# peripherals.net
KiCad netlist of a schematic drawn in Altium Designer
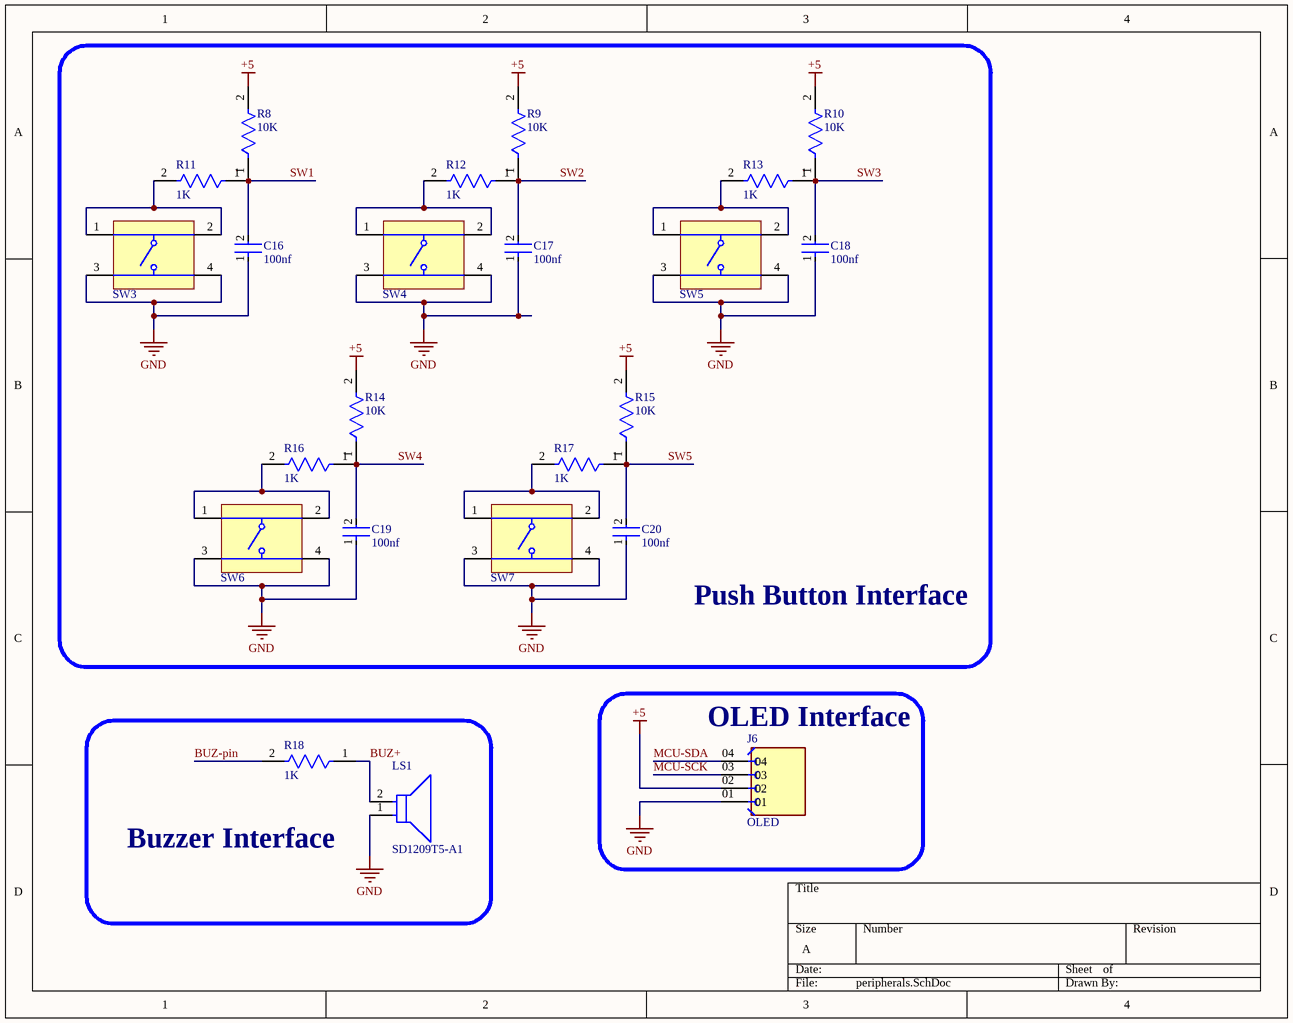
[diagram p0: peripherals.SchDoc]

(export (version "E")
  (design (tool "Eeschema 10.0.6"))
  (components
    (comp (ref "C16")
      (value "100nf")
      (footprint "FP-CC0805-0_85-MFG")
      (description "CAP CER 0.1UF 50V X7R 0805")
      (fields (field (name "TOLERANCE") "0.1") (field (name "MANUFACTURER PART NUMBER") "CC0805KRX7R9BB104"))
      (libsource (lib "Altium Content Vault") (part "11868f565c42a9108669ba33697ecf6"))
    )
    (comp (ref "C17")
      (value "100nf")
      (footprint "FP-CC0805-0_85-MFG")
      (description "CAP CER 0.1UF 50V X7R 0805")
      (fields (field (name "TOLERANCE") "0.1") (field (name "MANUFACTURER PART NUMBER") "CC0805KRX7R9BB104"))
      (libsource (lib "Altium Content Vault") (part "11868f565c42a9108669ba33697ecf6"))
    )
    (comp (ref "C18")
      (value "100nf")
      (footprint "FP-CC0805-0_85-MFG")
      (description "CAP CER 0.1UF 50V X7R 0805")
      (fields (field (name "TOLERANCE") "0.1") (field (name "MANUFACTURER PART NUMBER") "CC0805KRX7R9BB104"))
      (libsource (lib "Altium Content Vault") (part "11868f565c42a9108669ba33697ecf6"))
    )
    (comp (ref "C19")
      (value "100nf")
      (footprint "FP-CC0805-0_85-MFG")
      (description "CAP CER 0.1UF 50V X7R 0805")
      (fields (field (name "TOLERANCE") "0.1") (field (name "MANUFACTURER PART NUMBER") "CC0805KRX7R9BB104"))
      (libsource (lib "Altium Content Vault") (part "11868f565c42a9108669ba33697ecf6"))
    )
    (comp (ref "C20")
      (value "100nf")
      (footprint "FP-CC0805-0_85-MFG")
      (description "CAP CER 0.1UF 50V X7R 0805")
      (fields (field (name "TOLERANCE") "0.1") (field (name "MANUFACTURER PART NUMBER") "CC0805KRX7R9BB104"))
      (libsource (lib "Altium Content Vault") (part "11868f565c42a9108669ba33697ecf6"))
    )
    (comp (ref "J6")
      (value "OLED")
      (footprint "AMPHENOL_75915-804")
      (fields (field (name "MF") "Amphenol") (field (name "MP") "75915-804"))
      (libsource (lib "1x4 female pin header") (part "75915-804"))
    )
    (comp (ref "LS1")
      (value "SD1209T5-A1")
      (footprint "FP-SD1209-MFG")
      (description "AUDIO MAGNETIC XDCR 3-6V TH")
      (libsource (lib "Altium Content Vault") (part "1973c4b650225fd2ddacaff6b763965"))
    )
    (comp (ref "R8")
      (value "10K")
      (footprint "FP-CRCW0805-e3-MFG")
      (description "RES Thick Film, 100kΩ, 1%, 0.125W, 100ppm/°C, 0805")
      (fields (field (name "TOLERANCE") "1%"))
      (libsource (lib "Altium Content Vault") (part "1029c3af85768c4190bb7ad29bc67b5"))
    )
    (comp (ref "R9")
      (value "10K")
      (footprint "FP-CRCW0805-e3-MFG")
      (description "RES Thick Film, 100kΩ, 1%, 0.125W, 100ppm/°C, 0805")
      (fields (field (name "TOLERANCE") "1%"))
      (libsource (lib "Altium Content Vault") (part "1029c3af85768c4190bb7ad29bc67b5"))
    )
    (comp (ref "R10")
      (value "10K")
      (footprint "FP-CRCW0805-e3-MFG")
      (description "RES Thick Film, 100kΩ, 1%, 0.125W, 100ppm/°C, 0805")
      (fields (field (name "TOLERANCE") "1%"))
      (libsource (lib "Altium Content Vault") (part "1029c3af85768c4190bb7ad29bc67b5"))
    )
    (comp (ref "R11")
      (value "1K")
      (footprint "FP-CRCW0805-e3-MFG")
      (description "RES Thick Film, 100kΩ, 1%, 0.125W, 100ppm/°C, 0805")
      (fields (field (name "TOLERANCE") "1%"))
      (libsource (lib "Altium Content Vault") (part "1029c3af85768c4190bb7ad29bc67b5"))
    )
    (comp (ref "R12")
      (value "1K")
      (footprint "FP-CRCW0805-e3-MFG")
      (description "RES Thick Film, 100kΩ, 1%, 0.125W, 100ppm/°C, 0805")
      (fields (field (name "TOLERANCE") "1%"))
      (libsource (lib "Altium Content Vault") (part "1029c3af85768c4190bb7ad29bc67b5"))
    )
    (comp (ref "R13")
      (value "1K")
      (footprint "FP-CRCW0805-e3-MFG")
      (description "RES Thick Film, 100kΩ, 1%, 0.125W, 100ppm/°C, 0805")
      (fields (field (name "TOLERANCE") "1%"))
      (libsource (lib "Altium Content Vault") (part "1029c3af85768c4190bb7ad29bc67b5"))
    )
    (comp (ref "R14")
      (value "10K")
      (footprint "FP-CRCW0805-e3-MFG")
      (description "RES Thick Film, 100kΩ, 1%, 0.125W, 100ppm/°C, 0805")
      (fields (field (name "TOLERANCE") "1%"))
      (libsource (lib "Altium Content Vault") (part "1029c3af85768c4190bb7ad29bc67b5"))
    )
    (comp (ref "R15")
      (value "10K")
      (footprint "FP-CRCW0805-e3-MFG")
      (description "RES Thick Film, 100kΩ, 1%, 0.125W, 100ppm/°C, 0805")
      (fields (field (name "TOLERANCE") "1%"))
      (libsource (lib "Altium Content Vault") (part "1029c3af85768c4190bb7ad29bc67b5"))
    )
    (comp (ref "R16")
      (value "1K")
      (footprint "FP-CRCW0805-e3-MFG")
      (description "RES Thick Film, 100kΩ, 1%, 0.125W, 100ppm/°C, 0805")
      (fields (field (name "TOLERANCE") "1%"))
      (libsource (lib "Altium Content Vault") (part "1029c3af85768c4190bb7ad29bc67b5"))
    )
    (comp (ref "R17")
      (value "1K")
      (footprint "FP-CRCW0805-e3-MFG")
      (description "RES Thick Film, 100kΩ, 1%, 0.125W, 100ppm/°C, 0805")
      (fields (field (name "TOLERANCE") "1%"))
      (libsource (lib "Altium Content Vault") (part "1029c3af85768c4190bb7ad29bc67b5"))
    )
    (comp (ref "R18")
      (value "1K")
      (footprint "FP-CRCW0805-e3-MFG")
      (description "RES Thick Film, 100kΩ, 1%, 0.125W, 100ppm/°C, 0805")
      (fields (field (name "TOLERANCE") "1%"))
      (libsource (lib "Altium Content Vault") (part "1029c3af85768c4190bb7ad29bc67b5"))
    )
    (comp (ref "SW3")
      (value "FSM4JSMATR")
      (footprint "TECO-FSM4JSMATR_V")
      (description "Micro Miniature Push Button Switch FSM JSM, 50 mA, -35 to 85 degC, 4-Pin SMD, RoHS, Tape and Reel")
      (fields (field (name "MANUFACTURER") "TE Connectivity"))
      (libsource (lib "Altium Content Vault") (part "SW-SPST-4_A"))
    )
    (comp (ref "SW4")
      (value "FSM4JSMATR")
      (footprint "TECO-FSM4JSMATR_V")
      (description "Micro Miniature Push Button Switch FSM JSM, 50 mA, -35 to 85 degC, 4-Pin SMD, RoHS, Tape and Reel")
      (fields (field (name "MANUFACTURER") "TE Connectivity"))
      (libsource (lib "Altium Content Vault") (part "SW-SPST-4_A"))
    )
    (comp (ref "SW5")
      (value "FSM4JSMATR")
      (footprint "TECO-FSM4JSMATR_V")
      (description "Micro Miniature Push Button Switch FSM JSM, 50 mA, -35 to 85 degC, 4-Pin SMD, RoHS, Tape and Reel")
      (fields (field (name "MANUFACTURER") "TE Connectivity"))
      (libsource (lib "Altium Content Vault") (part "SW-SPST-4_A"))
    )
    (comp (ref "SW6")
      (value "FSM4JSMATR")
      (footprint "TECO-FSM4JSMATR_V")
      (description "Micro Miniature Push Button Switch FSM JSM, 50 mA, -35 to 85 degC, 4-Pin SMD, RoHS, Tape and Reel")
      (fields (field (name "MANUFACTURER") "TE Connectivity"))
      (libsource (lib "Altium Content Vault") (part "SW-SPST-4_A"))
    )
    (comp (ref "SW7")
      (value "FSM4JSMATR")
      (footprint "TECO-FSM4JSMATR_V")
      (description "Micro Miniature Push Button Switch FSM JSM, 50 mA, -35 to 85 degC, 4-Pin SMD, RoHS, Tape and Reel")
      (fields (field (name "MANUFACTURER") "TE Connectivity"))
      (libsource (lib "Altium Content Vault") (part "SW-SPST-4_A"))
    )
  )
  (nets
    (net (code "1") (name "+5") (class "Default")
      (node (ref "J6") (pin "02") (pinfunction "02_02") (pintype "passive"))
      (node (ref "R10") (pin "2") (pinfunction "2_2") (pintype "passive"))
      (node (ref "R14") (pin "2") (pinfunction "2_2") (pintype "passive"))
      (node (ref "R15") (pin "2") (pinfunction "2_2") (pintype "passive"))
      (node (ref "R8") (pin "2") (pinfunction "2_2") (pintype "passive"))
      (node (ref "R9") (pin "2") (pinfunction "2_2") (pintype "passive"))
    )
    (net (code "2") (name "/BUZ+") (class "Default")
      (node (ref "LS1") (pin "2") (pinfunction "A_2") (pintype "passive"))
      (node (ref "R18") (pin "1") (pinfunction "1_1") (pintype "passive"))
    )
    (net (code "3") (name "/BUZ-pin") (class "Default")
      (node (ref "R18") (pin "2") (pinfunction "2_2") (pintype "passive"))
    )
    (net (code "4") (name "/MCU-SCK") (class "Default")
      (node (ref "J6") (pin "03") (pinfunction "03_03") (pintype "passive"))
    )
    (net (code "5") (name "/MCU-SDA") (class "Default")
      (node (ref "J6") (pin "04") (pinfunction "04_04") (pintype "passive"))
    )
    (net (code "6") (name "/SW1") (class "Default")
      (node (ref "C16") (pin "2") (pinfunction "2_2") (pintype "passive"))
      (node (ref "R11") (pin "1") (pinfunction "1_1") (pintype "passive"))
      (node (ref "R8") (pin "1") (pinfunction "1_1") (pintype "passive"))
    )
    (net (code "7") (name "/SW2") (class "Default")
      (node (ref "C17") (pin "2") (pinfunction "2_2") (pintype "passive"))
      (node (ref "R12") (pin "1") (pinfunction "1_1") (pintype "passive"))
      (node (ref "R9") (pin "1") (pinfunction "1_1") (pintype "passive"))
    )
    (net (code "8") (name "/SW3") (class "Default")
      (node (ref "C18") (pin "2") (pinfunction "2_2") (pintype "passive"))
      (node (ref "R10") (pin "1") (pinfunction "1_1") (pintype "passive"))
      (node (ref "R13") (pin "1") (pinfunction "1_1") (pintype "passive"))
    )
    (net (code "9") (name "/SW4") (class "Default")
      (node (ref "C19") (pin "2") (pinfunction "2_2") (pintype "passive"))
      (node (ref "R14") (pin "1") (pinfunction "1_1") (pintype "passive"))
      (node (ref "R16") (pin "1") (pinfunction "1_1") (pintype "passive"))
    )
    (net (code "10") (name "/SW5") (class "Default")
      (node (ref "C20") (pin "2") (pinfunction "2_2") (pintype "passive"))
      (node (ref "R15") (pin "1") (pinfunction "1_1") (pintype "passive"))
      (node (ref "R17") (pin "1") (pinfunction "1_1") (pintype "passive"))
    )
    (net (code "11") (name "GND") (class "Default")
      (node (ref "C16") (pin "1") (pinfunction "1_1") (pintype "passive"))
      (node (ref "C17") (pin "1") (pinfunction "1_1") (pintype "passive"))
      (node (ref "C18") (pin "1") (pinfunction "1_1") (pintype "passive"))
      (node (ref "C19") (pin "1") (pinfunction "1_1") (pintype "passive"))
      (node (ref "C20") (pin "1") (pinfunction "1_1") (pintype "passive"))
      (node (ref "J6") (pin "01") (pinfunction "01_01") (pintype "passive"))
      (node (ref "LS1") (pin "1") (pinfunction "C_1") (pintype "passive"))
      (node (ref "SW3") (pin "3") (pinfunction "3_3") (pintype "passive"))
      (node (ref "SW3") (pin "4") (pinfunction "4_4") (pintype "passive"))
      (node (ref "SW4") (pin "3") (pinfunction "3_3") (pintype "passive"))
      (node (ref "SW4") (pin "4") (pinfunction "4_4") (pintype "passive"))
      (node (ref "SW5") (pin "3") (pinfunction "3_3") (pintype "passive"))
      (node (ref "SW5") (pin "4") (pinfunction "4_4") (pintype "passive"))
      (node (ref "SW6") (pin "3") (pinfunction "3_3") (pintype "passive"))
      (node (ref "SW6") (pin "4") (pinfunction "4_4") (pintype "passive"))
      (node (ref "SW7") (pin "3") (pinfunction "3_3") (pintype "passive"))
      (node (ref "SW7") (pin "4") (pinfunction "4_4") (pintype "passive"))
    )
    (net (code "12") (name "Net-(R11-Pad2)") (class "Default")
      (node (ref "R11") (pin "2") (pinfunction "2_2") (pintype "passive"))
      (node (ref "SW3") (pin "1") (pinfunction "1_1") (pintype "passive"))
      (node (ref "SW3") (pin "2") (pinfunction "2_2") (pintype "passive"))
    )
    (net (code "13") (name "Net-(R12-Pad2)") (class "Default")
      (node (ref "R12") (pin "2") (pinfunction "2_2") (pintype "passive"))
      (node (ref "SW4") (pin "1") (pinfunction "1_1") (pintype "passive"))
      (node (ref "SW4") (pin "2") (pinfunction "2_2") (pintype "passive"))
    )
    (net (code "14") (name "Net-(R13-Pad2)") (class "Default")
      (node (ref "R13") (pin "2") (pinfunction "2_2") (pintype "passive"))
      (node (ref "SW5") (pin "1") (pinfunction "1_1") (pintype "passive"))
      (node (ref "SW5") (pin "2") (pinfunction "2_2") (pintype "passive"))
    )
    (net (code "15") (name "Net-(R16-Pad2)") (class "Default")
      (node (ref "R16") (pin "2") (pinfunction "2_2") (pintype "passive"))
      (node (ref "SW6") (pin "1") (pinfunction "1_1") (pintype "passive"))
      (node (ref "SW6") (pin "2") (pinfunction "2_2") (pintype "passive"))
    )
    (net (code "16") (name "Net-(R17-Pad2)") (class "Default")
      (node (ref "R17") (pin "2") (pinfunction "2_2") (pintype "passive"))
      (node (ref "SW7") (pin "1") (pinfunction "1_1") (pintype "passive"))
      (node (ref "SW7") (pin "2") (pinfunction "2_2") (pintype "passive"))
    )
  )
)
